# board2.net
KiCad netlist of a schematic drawn in EAGLE
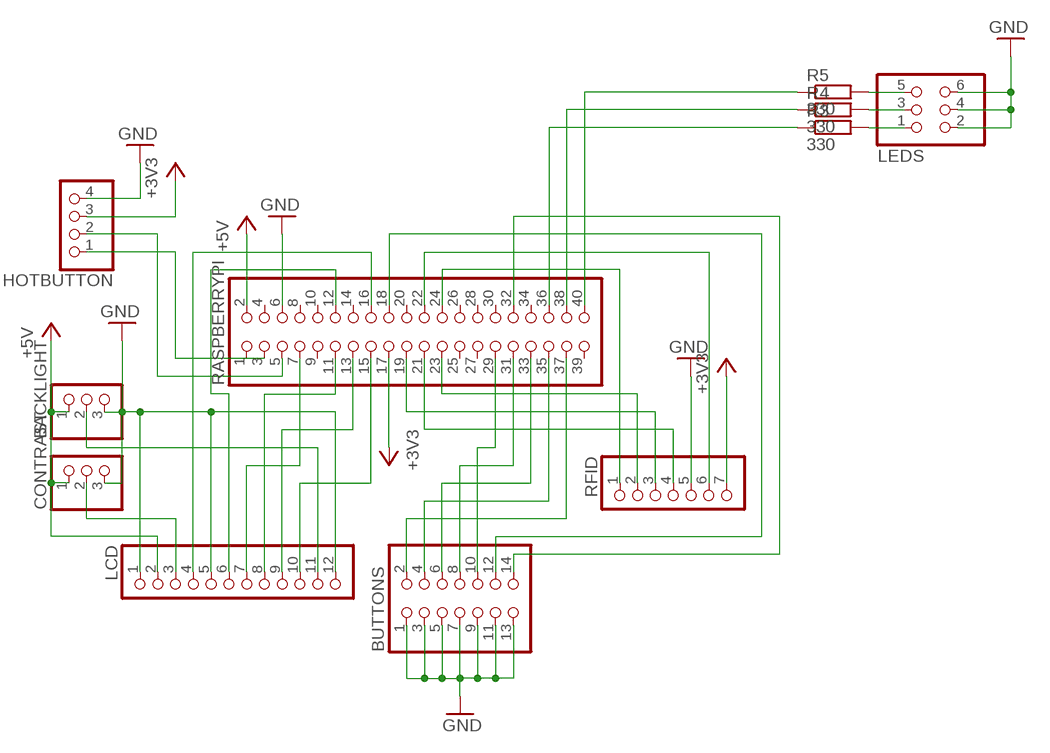
[diagram p0: schematic, sheet 1]

(export (version "E")
  (design (tool "Eeschema 10.0.6"))
  (components
    (comp (ref "BACKLIGHT")
      (value "PINHD-1X3")
      (footprint "eagle-import:1X03")
      (libsource (lib "eagle-import") (part "PINHD-1X3"))
    )
    (comp (ref "BUTTONS")
      (value "PINHD-2X7")
      (footprint "eagle-import:2X07")
      (libsource (lib "eagle-import") (part "PINHD-2X7"))
    )
    (comp (ref "CONTRAST")
      (value "PINHD-1X3")
      (footprint "eagle-import:1X03")
      (libsource (lib "eagle-import") (part "PINHD-1X3"))
    )
    (comp (ref "HOTBUTTON")
      (value "PINHD-1X4")
      (footprint "eagle-import:1X04")
      (libsource (lib "eagle-import") (part "PINHD-1X4"))
    )
    (comp (ref "LCD")
      (value "PINHD-1X12")
      (footprint "eagle-import:1X12")
      (libsource (lib "eagle-import") (part "PINHD-1X12"))
    )
    (comp (ref "LEDS")
      (value "PINHD-2X3")
      (footprint "eagle-import:2X03")
      (libsource (lib "eagle-import") (part "PINHD-2X3"))
    )
    (comp (ref "R3")
      (value "330")
      (footprint "eagle-import:0207_10")
      (libsource (lib "eagle-import") (part "R-EU_0207/10"))
    )
    (comp (ref "R4")
      (value "330")
      (footprint "eagle-import:0207_10")
      (libsource (lib "eagle-import") (part "R-EU_0207/10"))
    )
    (comp (ref "R5")
      (value "330")
      (footprint "eagle-import:0207_10")
      (libsource (lib "eagle-import") (part "R-EU_0207/10"))
    )
    (comp (ref "RASPBERRYPI")
      (value "PINHD-2X20")
      (footprint "eagle-import:2X20")
      (libsource (lib "eagle-import") (part "PINHD-2X20"))
    )
    (comp (ref "RFID")
      (value "PINHD-1X7")
      (footprint "eagle-import:1X07")
      (libsource (lib "eagle-import") (part "PINHD-1X7"))
    )
  )
  (nets
    (net (code "1") (name "+3V3") (class "Default")
      (node (ref "HOTBUTTON") (pin "3") (pinfunction "3_3") (pintype "passive"))
      (node (ref "RASPBERRYPI") (pin "17") (pinfunction "17_17") (pintype "passive"))
      (node (ref "RFID") (pin "7") (pinfunction "7_7") (pintype "passive"))
    )
    (net (code "2") (name "+5V") (class "Default")
      (node (ref "BACKLIGHT") (pin "1") (pinfunction "1_1") (pintype "passive"))
      (node (ref "CONTRAST") (pin "1") (pinfunction "1_1") (pintype "passive"))
      (node (ref "LCD") (pin "2") (pinfunction "2_2") (pintype "passive"))
      (node (ref "RASPBERRYPI") (pin "2") (pinfunction "2_2") (pintype "passive"))
    )
    (net (code "3") (name "GND") (class "Default")
      (node (ref "BACKLIGHT") (pin "3") (pinfunction "3_3") (pintype "passive"))
      (node (ref "BUTTONS") (pin "1") (pinfunction "1_1") (pintype "passive"))
      (node (ref "BUTTONS") (pin "11") (pinfunction "11_11") (pintype "passive"))
      (node (ref "BUTTONS") (pin "13") (pinfunction "13_13") (pintype "passive"))
      (node (ref "BUTTONS") (pin "3") (pinfunction "3_3") (pintype "passive"))
      (node (ref "BUTTONS") (pin "5") (pinfunction "5_5") (pintype "passive"))
      (node (ref "BUTTONS") (pin "7") (pinfunction "7_7") (pintype "passive"))
      (node (ref "BUTTONS") (pin "9") (pinfunction "9_9") (pintype "passive"))
      (node (ref "CONTRAST") (pin "3") (pinfunction "3_3") (pintype "passive"))
      (node (ref "HOTBUTTON") (pin "4") (pinfunction "4_4") (pintype "passive"))
      (node (ref "LCD") (pin "1") (pinfunction "1_1") (pintype "passive"))
      (node (ref "LCD") (pin "12") (pinfunction "12_12") (pintype "passive"))
      (node (ref "LCD") (pin "5") (pinfunction "5_5") (pintype "passive"))
      (node (ref "LEDS") (pin "2") (pinfunction "2_2") (pintype "passive"))
      (node (ref "LEDS") (pin "4") (pinfunction "4_4") (pintype "passive"))
      (node (ref "LEDS") (pin "6") (pinfunction "6_6") (pintype "passive"))
      (node (ref "RASPBERRYPI") (pin "6") (pinfunction "6_6") (pintype "passive"))
      (node (ref "RFID") (pin "5") (pinfunction "5_5") (pintype "passive"))
    )
    (net (code "4") (name "Net-(BACKLIGHT-Pad2)") (class "Default")
      (node (ref "BACKLIGHT") (pin "2") (pinfunction "2_2") (pintype "passive"))
      (node (ref "LCD") (pin "11") (pinfunction "11_11") (pintype "passive"))
    )
    (net (code "5") (name "Net-(BUTTONS-Pad2)") (class "Default")
      (node (ref "BUTTONS") (pin "2") (pinfunction "2_2") (pintype "passive"))
      (node (ref "RASPBERRYPI") (pin "37") (pinfunction "37_37") (pintype "passive"))
    )
    (net (code "6") (name "Net-(BUTTONS-Pad4)") (class "Default")
      (node (ref "BUTTONS") (pin "4") (pinfunction "4_4") (pintype "passive"))
      (node (ref "RASPBERRYPI") (pin "35") (pinfunction "35_35") (pintype "passive"))
    )
    (net (code "7") (name "Net-(BUTTONS-Pad6)") (class "Default")
      (node (ref "BUTTONS") (pin "6") (pinfunction "6_6") (pintype "passive"))
      (node (ref "RASPBERRYPI") (pin "33") (pinfunction "33_33") (pintype "passive"))
    )
    (net (code "8") (name "Net-(BUTTONS-Pad8)") (class "Default")
      (node (ref "BUTTONS") (pin "8") (pinfunction "8_8") (pintype "passive"))
      (node (ref "RASPBERRYPI") (pin "31") (pinfunction "31_31") (pintype "passive"))
    )
    (net (code "9") (name "Net-(BUTTONS-Pad10)") (class "Default")
      (node (ref "BUTTONS") (pin "10") (pinfunction "10_10") (pintype "passive"))
      (node (ref "RASPBERRYPI") (pin "29") (pinfunction "29_29") (pintype "passive"))
    )
    (net (code "10") (name "Net-(BUTTONS-Pad12)") (class "Default")
      (node (ref "BUTTONS") (pin "12") (pinfunction "12_12") (pintype "passive"))
      (node (ref "RASPBERRYPI") (pin "18") (pinfunction "18_18") (pintype "passive"))
    )
    (net (code "11") (name "Net-(BUTTONS-Pad14)") (class "Default")
      (node (ref "BUTTONS") (pin "14") (pinfunction "14_14") (pintype "passive"))
      (node (ref "RASPBERRYPI") (pin "32") (pinfunction "32_32") (pintype "passive"))
    )
    (net (code "12") (name "Net-(CONTRAST-Pad2)") (class "Default")
      (node (ref "CONTRAST") (pin "2") (pinfunction "2_2") (pintype "passive"))
      (node (ref "LCD") (pin "3") (pinfunction "3_3") (pintype "passive"))
    )
    (net (code "13") (name "Net-(HOTBUTTON-Pad1)") (class "Default")
      (node (ref "HOTBUTTON") (pin "1") (pinfunction "1_1") (pintype "passive"))
      (node (ref "RASPBERRYPI") (pin "3") (pinfunction "3_3") (pintype "passive"))
    )
    (net (code "14") (name "Net-(HOTBUTTON-Pad2)") (class "Default")
      (node (ref "HOTBUTTON") (pin "2") (pinfunction "2_2") (pintype "passive"))
      (node (ref "RASPBERRYPI") (pin "5") (pinfunction "5_5") (pintype "passive"))
    )
    (net (code "15") (name "Net-(LCD-Pad4)") (class "Default")
      (node (ref "LCD") (pin "4") (pinfunction "4_4") (pintype "passive"))
      (node (ref "RASPBERRYPI") (pin "16") (pinfunction "16_16") (pintype "passive"))
    )
    (net (code "16") (name "Net-(LCD-Pad6)") (class "Default")
      (node (ref "LCD") (pin "6") (pinfunction "6_6") (pintype "passive"))
      (node (ref "RASPBERRYPI") (pin "12") (pinfunction "12_12") (pintype "passive"))
    )
    (net (code "17") (name "Net-(LCD-Pad7)") (class "Default")
      (node (ref "LCD") (pin "7") (pinfunction "7_7") (pintype "passive"))
      (node (ref "RASPBERRYPI") (pin "7") (pinfunction "7_7") (pintype "passive"))
    )
    (net (code "18") (name "Net-(LCD-Pad8)") (class "Default")
      (node (ref "LCD") (pin "8") (pinfunction "8_8") (pintype "passive"))
      (node (ref "RASPBERRYPI") (pin "11") (pinfunction "11_11") (pintype "passive"))
    )
    (net (code "19") (name "Net-(LCD-Pad9)") (class "Default")
      (node (ref "LCD") (pin "9") (pinfunction "9_9") (pintype "passive"))
      (node (ref "RASPBERRYPI") (pin "13") (pinfunction "13_13") (pintype "passive"))
    )
    (net (code "20") (name "Net-(LCD-Pad10)") (class "Default")
      (node (ref "LCD") (pin "10") (pinfunction "10_10") (pintype "passive"))
      (node (ref "RASPBERRYPI") (pin "15") (pinfunction "15_15") (pintype "passive"))
    )
    (net (code "21") (name "Net-(LEDS-Pad1)") (class "Default")
      (node (ref "LEDS") (pin "1") (pinfunction "1_1") (pintype "passive"))
      (node (ref "R3") (pin "2") (pinfunction "2_2") (pintype "passive"))
    )
    (net (code "22") (name "Net-(LEDS-Pad3)") (class "Default")
      (node (ref "LEDS") (pin "3") (pinfunction "3_3") (pintype "passive"))
      (node (ref "R4") (pin "2") (pinfunction "2_2") (pintype "passive"))
    )
    (net (code "23") (name "Net-(LEDS-Pad5)") (class "Default")
      (node (ref "LEDS") (pin "5") (pinfunction "5_5") (pintype "passive"))
      (node (ref "R5") (pin "2") (pinfunction "2_2") (pintype "passive"))
    )
    (net (code "24") (name "Net-(R3-Pad1)") (class "Default")
      (node (ref "R3") (pin "1") (pinfunction "1_1") (pintype "passive"))
      (node (ref "RASPBERRYPI") (pin "36") (pinfunction "36_36") (pintype "passive"))
    )
    (net (code "25") (name "Net-(R4-Pad1)") (class "Default")
      (node (ref "R4") (pin "1") (pinfunction "1_1") (pintype "passive"))
      (node (ref "RASPBERRYPI") (pin "38") (pinfunction "38_38") (pintype "passive"))
    )
    (net (code "26") (name "Net-(R5-Pad1)") (class "Default")
      (node (ref "R5") (pin "1") (pinfunction "1_1") (pintype "passive"))
      (node (ref "RASPBERRYPI") (pin "40") (pinfunction "40_40") (pintype "passive"))
    )
    (net (code "27") (name "Net-(RASPBERRYPI-Pad19)") (class "Default")
      (node (ref "RASPBERRYPI") (pin "19") (pinfunction "19_19") (pintype "passive"))
      (node (ref "RFID") (pin "3") (pinfunction "3_3") (pintype "passive"))
    )
    (net (code "28") (name "Net-(RASPBERRYPI-Pad21)") (class "Default")
      (node (ref "RASPBERRYPI") (pin "21") (pinfunction "21_21") (pintype "passive"))
      (node (ref "RFID") (pin "4") (pinfunction "4_4") (pintype "passive"))
    )
    (net (code "29") (name "Net-(RASPBERRYPI-Pad22)") (class "Default")
      (node (ref "RASPBERRYPI") (pin "22") (pinfunction "22_22") (pintype "passive"))
      (node (ref "RFID") (pin "6") (pinfunction "6_6") (pintype "passive"))
    )
    (net (code "30") (name "Net-(RASPBERRYPI-Pad23)") (class "Default")
      (node (ref "RASPBERRYPI") (pin "23") (pinfunction "23_23") (pintype "passive"))
      (node (ref "RFID") (pin "2") (pinfunction "2_2") (pintype "passive"))
    )
    (net (code "31") (name "Net-(RASPBERRYPI-Pad24)") (class "Default")
      (node (ref "RASPBERRYPI") (pin "24") (pinfunction "24_24") (pintype "passive"))
      (node (ref "RFID") (pin "1") (pinfunction "1_1") (pintype "passive"))
    )
    (net (code "32") (name "unconnected-(RASPBERRYPI-Pad1)") (class "Default")
      (node (ref "RASPBERRYPI") (pin "1") (pinfunction "1_1") (pintype "passive"))
    )
    (net (code "33") (name "unconnected-(RASPBERRYPI-Pad4)") (class "Default")
      (node (ref "RASPBERRYPI") (pin "4") (pinfunction "4_4") (pintype "passive"))
    )
    (net (code "34") (name "unconnected-(RASPBERRYPI-Pad8)") (class "Default")
      (node (ref "RASPBERRYPI") (pin "8") (pinfunction "8_8") (pintype "passive"))
    )
    (net (code "35") (name "unconnected-(RASPBERRYPI-Pad9)") (class "Default")
      (node (ref "RASPBERRYPI") (pin "9") (pinfunction "9_9") (pintype "passive"))
    )
    (net (code "36") (name "unconnected-(RASPBERRYPI-Pad10)") (class "Default")
      (node (ref "RASPBERRYPI") (pin "10") (pinfunction "10_10") (pintype "passive"))
    )
    (net (code "37") (name "unconnected-(RASPBERRYPI-Pad14)") (class "Default")
      (node (ref "RASPBERRYPI") (pin "14") (pinfunction "14_14") (pintype "passive"))
    )
    (net (code "38") (name "unconnected-(RASPBERRYPI-Pad20)") (class "Default")
      (node (ref "RASPBERRYPI") (pin "20") (pinfunction "20_20") (pintype "passive"))
    )
    (net (code "39") (name "unconnected-(RASPBERRYPI-Pad25)") (class "Default")
      (node (ref "RASPBERRYPI") (pin "25") (pinfunction "25_25") (pintype "passive"))
    )
    (net (code "40") (name "unconnected-(RASPBERRYPI-Pad26)") (class "Default")
      (node (ref "RASPBERRYPI") (pin "26") (pinfunction "26_26") (pintype "passive"))
    )
    (net (code "41") (name "unconnected-(RASPBERRYPI-Pad27)") (class "Default")
      (node (ref "RASPBERRYPI") (pin "27") (pinfunction "27_27") (pintype "passive"))
    )
    (net (code "42") (name "unconnected-(RASPBERRYPI-Pad28)") (class "Default")
      (node (ref "RASPBERRYPI") (pin "28") (pinfunction "28_28") (pintype "passive"))
    )
    (net (code "43") (name "unconnected-(RASPBERRYPI-Pad30)") (class "Default")
      (node (ref "RASPBERRYPI") (pin "30") (pinfunction "30_30") (pintype "passive"))
    )
    (net (code "44") (name "unconnected-(RASPBERRYPI-Pad34)") (class "Default")
      (node (ref "RASPBERRYPI") (pin "34") (pinfunction "34_34") (pintype "passive"))
    )
    (net (code "45") (name "unconnected-(RASPBERRYPI-Pad39)") (class "Default")
      (node (ref "RASPBERRYPI") (pin "39") (pinfunction "39_39") (pintype "passive"))
    )
  )
)
